# Smart_Stepper_Fin_-_MCU_MKL04Z16VFK4.net
KiCad netlist of a schematic drawn in Altium Designer
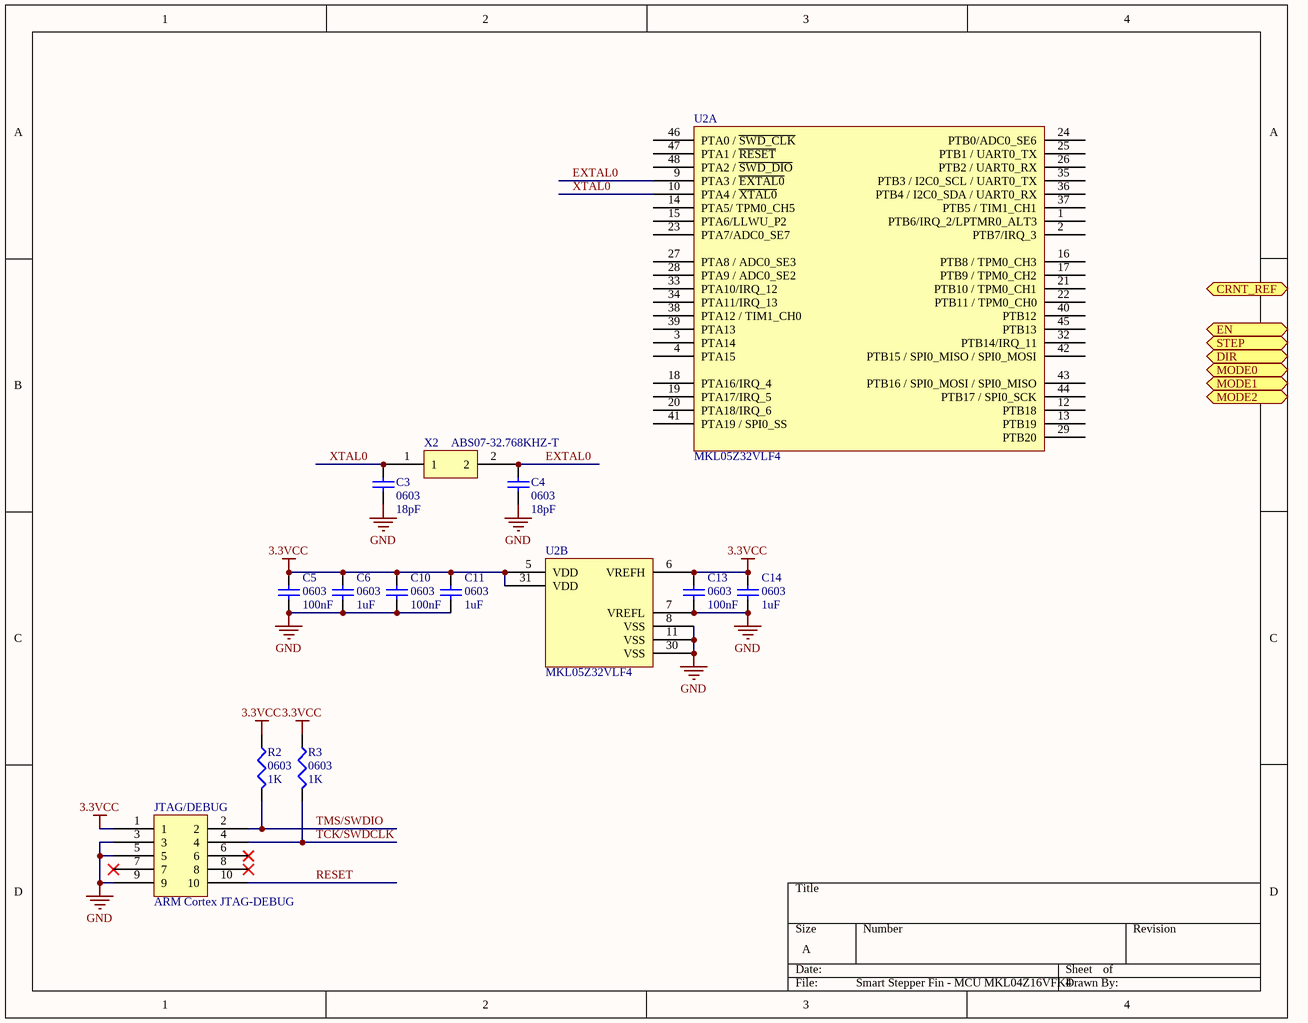
[diagram p0: Smart Stepper Fin - MCU MKL04Z16VFK4 .SchDoc]

(export (version "E")
  (design (tool "Eeschema 10.0.6"))
  (components
    (comp (ref "C3")
      (value "0603")
      (footprint "1608[0603]")
      (description "Capacitor (Semiconductor SIM Model)")
      (fields (field (name "ALTIUM_VALUE") "18pF") (field (name "PUBLISHER") "Altium Limited"))
      (libsource (lib "Miscellaneous Devices") (part "Cap Semi"))
    )
    (comp (ref "C4")
      (value "0603")
      (footprint "1608[0603]")
      (description "Capacitor (Semiconductor SIM Model)")
      (fields (field (name "ALTIUM_VALUE") "18pF") (field (name "PUBLISHER") "Altium Limited"))
      (libsource (lib "Miscellaneous Devices") (part "Cap Semi"))
    )
    (comp (ref "C5")
      (value "0603")
      (footprint "1608[0603]")
      (description "Capacitor (Semiconductor SIM Model)")
      (fields (field (name "ALTIUM_VALUE") "100nF") (field (name "PUBLISHER") "Altium Limited"))
      (libsource (lib "Miscellaneous Devices") (part "Cap Semi"))
    )
    (comp (ref "C6")
      (value "0603")
      (footprint "1608[0603]")
      (description "Capacitor (Semiconductor SIM Model)")
      (fields (field (name "ALTIUM_VALUE") "1uF") (field (name "PUBLISHER") "Altium Limited"))
      (libsource (lib "Miscellaneous Devices") (part "Cap Semi"))
    )
    (comp (ref "C10")
      (value "0603")
      (footprint "1608[0603]")
      (description "Capacitor (Semiconductor SIM Model)")
      (fields (field (name "ALTIUM_VALUE") "100nF") (field (name "PUBLISHER") "Altium Limited"))
      (libsource (lib "Miscellaneous Devices") (part "Cap Semi"))
    )
    (comp (ref "C11")
      (value "0603")
      (footprint "1608[0603]")
      (description "Capacitor (Semiconductor SIM Model)")
      (fields (field (name "ALTIUM_VALUE") "1uF") (field (name "PUBLISHER") "Altium Limited"))
      (libsource (lib "Miscellaneous Devices") (part "Cap Semi"))
    )
    (comp (ref "C13")
      (value "0603")
      (footprint "1608[0603]")
      (description "Capacitor (Semiconductor SIM Model)")
      (fields (field (name "ALTIUM_VALUE") "100nF") (field (name "PUBLISHER") "Altium Limited"))
      (libsource (lib "Miscellaneous Devices") (part "Cap Semi"))
    )
    (comp (ref "C14")
      (value "0603")
      (footprint "1608[0603]")
      (description "Capacitor (Semiconductor SIM Model)")
      (fields (field (name "ALTIUM_VALUE") "1uF") (field (name "PUBLISHER") "Altium Limited"))
      (libsource (lib "Miscellaneous Devices") (part "Cap Semi"))
    )
    (comp (ref "JTAG/DEBUG")
      (value "ARM Cortex JTAG-DEBUG")
      (footprint "FTSH-105-XX-X-DV")
      (libsource (lib "Adams Altium Library") (part "ARM Cortex JTAG-DEBUG Header"))
    )
    (comp (ref "R2")
      (value "0603")
      (footprint "J1-0603")
      (description "Resistor")
      (fields (field (name "ALTIUM_VALUE") "1K") (field (name "PUBLISHER") "Altium Limited"))
      (libsource (lib "Miscellaneous Devices") (part "Res3"))
    )
    (comp (ref "R3")
      (value "0603")
      (footprint "J1-0603")
      (description "Resistor")
      (fields (field (name "ALTIUM_VALUE") "1K") (field (name "PUBLISHER") "Altium Limited"))
      (libsource (lib "Miscellaneous Devices") (part "Res3"))
    )
    (comp (ref "U2")
      (value "MKL05Z32VLF4")
      (footprint "MKL05Z32VLF4")
      (description "ARM Cortex M0+")
      (libsource (lib "ExtruderFinLib") (part "MKL05Z32VLF4"))
    )
    (comp (ref "X2")
      (value "ABS07-32.768KHZ-T")
      (footprint "ABS07-32.768KHZ-T")
      (description "ABS07-32.768KHZ-T RTC Crystal Oscillator")
      (libsource (lib "Adams Altium Library") (part "ABS07-32.768KHZ-T"))
    )
  )
  (nets
    (net (code "4") (name "/EXTAL0") (class "Default")
      (node (ref "C4") (pin "1") (pinfunction "1_1") (pintype "passive"))
      (node (ref "U2") (pin "9") (pinfunction "PTA3_/_~{EXTAL0}_9") (pintype "passive"))
      (node (ref "X2") (pin "2") (pinfunction "2_2") (pintype "passive"))
    )
    (net (code "8") (name "/RESET") (class "Default")
      (node (ref "JTAG/DEBUG") (pin "10") (pinfunction "10_10") (pintype "passive"))
    )
    (net (code "10") (name "/TCK{slash}SWDCLK") (class "Default")
      (node (ref "JTAG/DEBUG") (pin "4") (pinfunction "4_4") (pintype "passive"))
      (node (ref "R3") (pin "2") (pinfunction "2_2") (pintype "passive"))
    )
    (net (code "11") (name "/TMS{slash}SWDIO") (class "Default")
      (node (ref "JTAG/DEBUG") (pin "2") (pinfunction "2_2") (pintype "passive"))
      (node (ref "R2") (pin "2") (pinfunction "2_2") (pintype "passive"))
    )
    (net (code "12") (name "/XTAL0") (class "Default")
      (node (ref "C3") (pin "1") (pinfunction "1_1") (pintype "passive"))
      (node (ref "U2") (pin "10") (pinfunction "PTA4_/_~{XTAL0}_10") (pintype "passive"))
      (node (ref "X2") (pin "1") (pinfunction "1_1") (pintype "passive"))
    )
    (net (code "13") (name "3.3VCC") (class "Default")
      (node (ref "C10") (pin "2") (pinfunction "2_2") (pintype "passive"))
      (node (ref "C11") (pin "2") (pinfunction "2_2") (pintype "passive"))
      (node (ref "C13") (pin "1") (pinfunction "1_1") (pintype "passive"))
      (node (ref "C14") (pin "1") (pinfunction "1_1") (pintype "passive"))
      (node (ref "C5") (pin "2") (pinfunction "2_2") (pintype "passive"))
      (node (ref "C6") (pin "2") (pinfunction "2_2") (pintype "passive"))
      (node (ref "JTAG/DEBUG") (pin "1") (pinfunction "1_1") (pintype "passive"))
      (node (ref "R2") (pin "1") (pinfunction "1_1") (pintype "passive"))
      (node (ref "R3") (pin "1") (pinfunction "1_1") (pintype "passive"))
      (node (ref "U2") (pin "31") (pinfunction "VDD_31") (pintype "passive"))
      (node (ref "U2") (pin "5") (pinfunction "VDD_5") (pintype "passive"))
      (node (ref "U2") (pin "6") (pinfunction "VREFH_6") (pintype "passive"))
    )
    (net (code "14") (name "GND") (class "Default")
      (node (ref "C10") (pin "1") (pinfunction "1_1") (pintype "passive"))
      (node (ref "C11") (pin "1") (pinfunction "1_1") (pintype "passive"))
      (node (ref "C13") (pin "2") (pinfunction "2_2") (pintype "passive"))
      (node (ref "C14") (pin "2") (pinfunction "2_2") (pintype "passive"))
      (node (ref "C3") (pin "2") (pinfunction "2_2") (pintype "passive"))
      (node (ref "C4") (pin "2") (pinfunction "2_2") (pintype "passive"))
      (node (ref "C5") (pin "1") (pinfunction "1_1") (pintype "passive"))
      (node (ref "C6") (pin "1") (pinfunction "1_1") (pintype "passive"))
      (node (ref "JTAG/DEBUG") (pin "3") (pinfunction "3_3") (pintype "passive"))
      (node (ref "JTAG/DEBUG") (pin "5") (pinfunction "5_5") (pintype "passive"))
      (node (ref "JTAG/DEBUG") (pin "9") (pinfunction "9_9") (pintype "passive"))
      (node (ref "U2") (pin "11") (pinfunction "VSS_11") (pintype "passive"))
      (node (ref "U2") (pin "30") (pinfunction "VSS_30") (pintype "passive"))
      (node (ref "U2") (pin "7") (pinfunction "VREFL_7") (pintype "passive"))
      (node (ref "U2") (pin "8") (pinfunction "VSS_8") (pintype "passive"))
    )
    (net (code "15") (name "unconnected-(JTAG/DEBUG-Pad6)") (class "Default")
      (node (ref "JTAG/DEBUG") (pin "6") (pinfunction "6_6") (pintype "passive+no_connect"))
    )
    (net (code "16") (name "unconnected-(JTAG/DEBUG-Pad7)") (class "Default")
      (node (ref "JTAG/DEBUG") (pin "7") (pinfunction "7_7") (pintype "passive+no_connect"))
    )
    (net (code "17") (name "unconnected-(JTAG/DEBUG-Pad8)") (class "Default")
      (node (ref "JTAG/DEBUG") (pin "8") (pinfunction "8_8") (pintype "passive+no_connect"))
    )
    (net (code "18") (name "unconnected-(U2A-PTA0_{slash}_~{SWD_CLK}-Pad46)") (class "Default")
      (node (ref "U2") (pin "46") (pinfunction "PTA0_/_~{SWD_CLK}_46") (pintype "passive"))
    )
    (net (code "19") (name "unconnected-(U2A-PTA1_{slash}_~{RESET}-Pad47)") (class "Default")
      (node (ref "U2") (pin "47") (pinfunction "PTA1_/_~{RESET}_47") (pintype "passive"))
    )
    (net (code "20") (name "unconnected-(U2A-PTA2_{slash}_~{SWD_DIO}-Pad48)") (class "Default")
      (node (ref "U2") (pin "48") (pinfunction "PTA2_/_~{SWD_DIO}_48") (pintype "passive"))
    )
    (net (code "21") (name "unconnected-(U2A-PTA5{slash}_TPM0_CH5-Pad14)") (class "Default")
      (node (ref "U2") (pin "14") (pinfunction "PTA5/_TPM0_CH5_14") (pintype "passive"))
    )
    (net (code "22") (name "unconnected-(U2A-PTA6{slash}LLWU_P2-Pad15)") (class "Default")
      (node (ref "U2") (pin "15") (pinfunction "PTA6/LLWU_P2_15") (pintype "passive"))
    )
    (net (code "23") (name "unconnected-(U2A-PTA7{slash}ADC0_SE7-Pad23)") (class "Default")
      (node (ref "U2") (pin "23") (pinfunction "PTA7/ADC0_SE7_23") (pintype "passive"))
    )
    (net (code "24") (name "unconnected-(U2A-PTA8_{slash}_ADC0_SE3-Pad27)") (class "Default")
      (node (ref "U2") (pin "27") (pinfunction "PTA8_/_ADC0_SE3_27") (pintype "passive"))
    )
    (net (code "25") (name "unconnected-(U2A-PTA9_{slash}_ADC0_SE2-Pad28)") (class "Default")
      (node (ref "U2") (pin "28") (pinfunction "PTA9_/_ADC0_SE2_28") (pintype "passive"))
    )
    (net (code "26") (name "unconnected-(U2A-PTA10{slash}IRQ_12-Pad33)") (class "Default")
      (node (ref "U2") (pin "33") (pinfunction "PTA10/IRQ_12_33") (pintype "passive"))
    )
    (net (code "27") (name "unconnected-(U2A-PTA11{slash}IRQ_13-Pad34)") (class "Default")
      (node (ref "U2") (pin "34") (pinfunction "PTA11/IRQ_13_34") (pintype "passive"))
    )
    (net (code "28") (name "unconnected-(U2A-PTA12_{slash}_TIM1_CH0-Pad38)") (class "Default")
      (node (ref "U2") (pin "38") (pinfunction "PTA12_/_TIM1_CH0_38") (pintype "passive"))
    )
    (net (code "29") (name "unconnected-(U2A-PTA13-Pad39)") (class "Default")
      (node (ref "U2") (pin "39") (pinfunction "PTA13_39") (pintype "passive"))
    )
    (net (code "30") (name "unconnected-(U2A-PTA14-Pad3)") (class "Default")
      (node (ref "U2") (pin "3") (pinfunction "PTA14_3") (pintype "passive"))
    )
    (net (code "31") (name "unconnected-(U2A-PTA15-Pad4)") (class "Default")
      (node (ref "U2") (pin "4") (pinfunction "PTA15_4") (pintype "passive"))
    )
    (net (code "32") (name "unconnected-(U2A-PTA16{slash}IRQ_4-Pad18)") (class "Default")
      (node (ref "U2") (pin "18") (pinfunction "PTA16/IRQ_4_18") (pintype "passive"))
    )
    (net (code "33") (name "unconnected-(U2A-PTA17{slash}IRQ_5-Pad19)") (class "Default")
      (node (ref "U2") (pin "19") (pinfunction "PTA17/IRQ_5_19") (pintype "passive"))
    )
    (net (code "34") (name "unconnected-(U2A-PTA18{slash}IRQ_6-Pad20)") (class "Default")
      (node (ref "U2") (pin "20") (pinfunction "PTA18/IRQ_6_20") (pintype "passive"))
    )
    (net (code "35") (name "unconnected-(U2A-PTA19_{slash}_SPI0_SS-Pad41)") (class "Default")
      (node (ref "U2") (pin "41") (pinfunction "PTA19_/_SPI0_SS_41") (pintype "passive"))
    )
    (net (code "36") (name "unconnected-(U2A-PTB0{slash}ADC0_SE6-Pad24)") (class "Default")
      (node (ref "U2") (pin "24") (pinfunction "PTB0/ADC0_SE6_24") (pintype "passive"))
    )
    (net (code "37") (name "unconnected-(U2A-PTB1_{slash}_UART0_TX-Pad25)") (class "Default")
      (node (ref "U2") (pin "25") (pinfunction "PTB1_/_UART0_TX_25") (pintype "passive"))
    )
    (net (code "38") (name "unconnected-(U2A-PTB2_{slash}_UART0_RX-Pad26)") (class "Default")
      (node (ref "U2") (pin "26") (pinfunction "PTB2_/_UART0_RX_26") (pintype "passive"))
    )
    (net (code "39") (name "unconnected-(U2A-PTB3_{slash}_I2C0_SCL_{slash}_UART0_TX-Pad35)") (class "Default")
      (node (ref "U2") (pin "35") (pinfunction "PTB3_/_I2C0_SCL_/_UART0_TX_35") (pintype "passive"))
    )
    (net (code "40") (name "unconnected-(U2A-PTB4_{slash}_I2C0_SDA_{slash}_UART0_RX-Pad36)") (class "Default")
      (node (ref "U2") (pin "36") (pinfunction "PTB4_/_I2C0_SDA_/_UART0_RX_36") (pintype "passive"))
    )
    (net (code "41") (name "unconnected-(U2A-PTB5_{slash}_TIM1_CH1-Pad37)") (class "Default")
      (node (ref "U2") (pin "37") (pinfunction "PTB5_/_TIM1_CH1_37") (pintype "passive"))
    )
    (net (code "42") (name "unconnected-(U2A-PTB6{slash}IRQ_2{slash}LPTMR0_ALT3-Pad1)") (class "Default")
      (node (ref "U2") (pin "1") (pinfunction "PTB6/IRQ_2/LPTMR0_ALT3_1") (pintype "passive"))
    )
    (net (code "43") (name "unconnected-(U2A-PTB7{slash}IRQ_3-Pad2)") (class "Default")
      (node (ref "U2") (pin "2") (pinfunction "PTB7/IRQ_3_2") (pintype "passive"))
    )
    (net (code "44") (name "unconnected-(U2A-PTB8_{slash}_TPM0_CH3-Pad16)") (class "Default")
      (node (ref "U2") (pin "16") (pinfunction "PTB8_/_TPM0_CH3_16") (pintype "passive"))
    )
    (net (code "45") (name "unconnected-(U2A-PTB9_{slash}_TPM0_CH2-Pad17)") (class "Default")
      (node (ref "U2") (pin "17") (pinfunction "PTB9_/_TPM0_CH2_17") (pintype "passive"))
    )
    (net (code "46") (name "unconnected-(U2A-PTB10_{slash}_TPM0_CH1-Pad21)") (class "Default")
      (node (ref "U2") (pin "21") (pinfunction "PTB10_/_TPM0_CH1_21") (pintype "passive"))
    )
    (net (code "47") (name "unconnected-(U2A-PTB11_{slash}_TPM0_CH0-Pad22)") (class "Default")
      (node (ref "U2") (pin "22") (pinfunction "PTB11_/_TPM0_CH0_22") (pintype "passive"))
    )
    (net (code "48") (name "unconnected-(U2A-PTB12-Pad40)") (class "Default")
      (node (ref "U2") (pin "40") (pinfunction "PTB12_40") (pintype "passive"))
    )
    (net (code "49") (name "unconnected-(U2A-PTB13-Pad45)") (class "Default")
      (node (ref "U2") (pin "45") (pinfunction "PTB13_45") (pintype "passive"))
    )
    (net (code "50") (name "unconnected-(U2A-PTB14{slash}IRQ_11-Pad32)") (class "Default")
      (node (ref "U2") (pin "32") (pinfunction "PTB14/IRQ_11_32") (pintype "passive"))
    )
    (net (code "51") (name "unconnected-(U2A-PTB15_{slash}_SPI0_MISO_{slash}_SPI0_MOSI-Pad42)") (class "Default")
      (node (ref "U2") (pin "42") (pinfunction "PTB15_/_SPI0_MISO_/_SPI0_MOSI_42") (pintype "passive"))
    )
    (net (code "52") (name "unconnected-(U2A-PTB16_{slash}_SPI0_MOSI_{slash}_SPI0_MISO-Pad43)") (class "Default")
      (node (ref "U2") (pin "43") (pinfunction "PTB16_/_SPI0_MOSI_/_SPI0_MISO_43") (pintype "passive"))
    )
    (net (code "53") (name "unconnected-(U2A-PTB17_{slash}_SPI0_SCK-Pad44)") (class "Default")
      (node (ref "U2") (pin "44") (pinfunction "PTB17_/_SPI0_SCK_44") (pintype "passive"))
    )
    (net (code "54") (name "unconnected-(U2A-PTB18-Pad12)") (class "Default")
      (node (ref "U2") (pin "12") (pinfunction "PTB18_12") (pintype "passive"))
    )
    (net (code "55") (name "unconnected-(U2A-PTB19-Pad13)") (class "Default")
      (node (ref "U2") (pin "13") (pinfunction "PTB19_13") (pintype "passive"))
    )
    (net (code "56") (name "unconnected-(U2A-PTB20-Pad29)") (class "Default")
      (node (ref "U2") (pin "29") (pinfunction "PTB20_29") (pintype "passive"))
    )
  )
)
